# MCU.net
KiCad netlist of a schematic drawn in Altium Designer
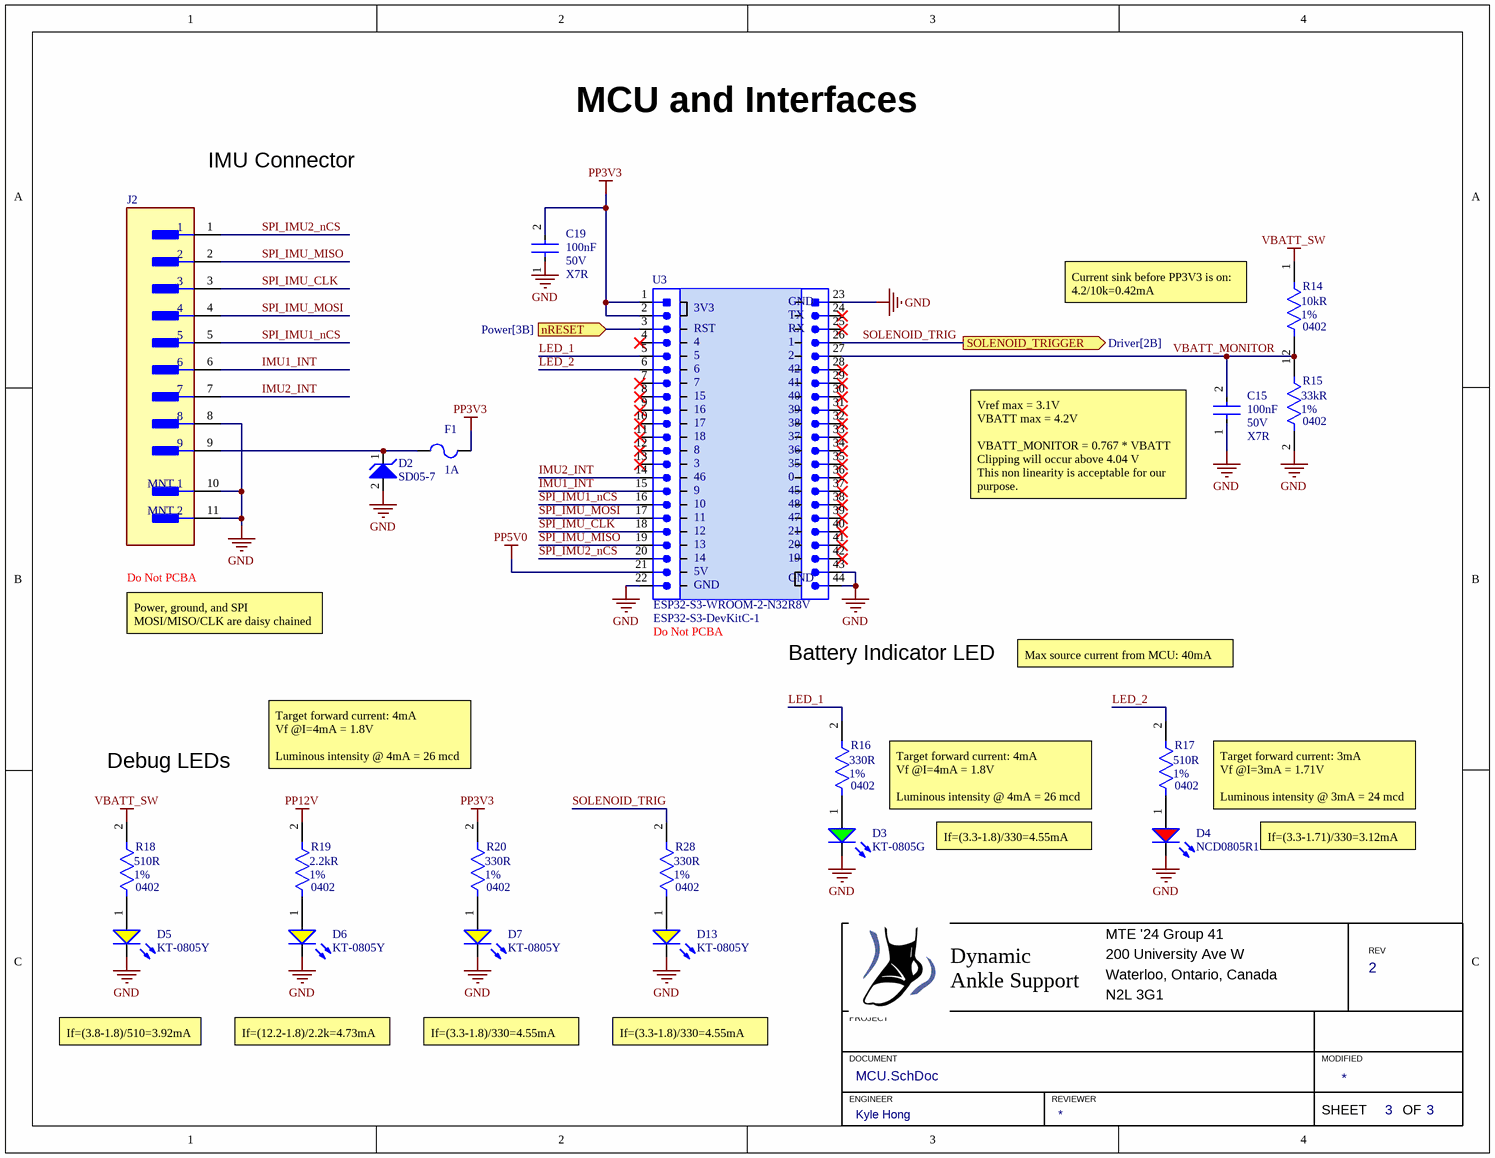
[diagram p0: MCU.SchDoc]

(export (version "E")
  (design (tool "Eeschema 10.0.6"))
  (components
    (comp (ref "C15")
      (value "CL05B104KB54PNC")
      (footprint "CAP0402")
      (description "50V 100nF X7R ±10% 0402  Multilayer Ceramic Capacitors MLCC - SMD/SMT ROHS")
      (fields
        (field (name "TOLERANCE") "±20%")
        (field (name "MANUFACTURER") "Samsung Electro-Mechanics")
        (field (name "DIELECTRIC") "X7R")
        (field (name "VOLTAGE RATING") "50V")
        (field (name "CAPACITANCE") "100nF")
      )
      (libsource (lib "FYDP_library_sch") (part "CAP0402"))
    )
    (comp (ref "C19")
      (value "CL05B104KB54PNC")
      (footprint "CAP0402")
      (description "50V 100nF X7R ±10% 0402  Multilayer Ceramic Capacitors MLCC - SMD/SMT ROHS")
      (fields
        (field (name "TOLERANCE") "±20%")
        (field (name "MANUFACTURER") "Samsung Electro-Mechanics")
        (field (name "DIELECTRIC") "X7R")
        (field (name "VOLTAGE RATING") "50V")
        (field (name "CAPACITANCE") "100nF")
      )
      (libsource (lib "FYDP_library_sch") (part "CAP0402"))
    )
    (comp (ref "D2")
      (value "SD05-7")
      (footprint "SD05-7")
      (description "TVS UNI14.5V 6.2V 5V SOD-323")
      (fields (field (name "MANUFACTURER") "Diodes Incorporated"))
      (libsource (lib "FYDP_library_sch") (part "SD05-7"))
    )
    (comp (ref "D3")
      (value "KT-0805G")
      (footprint "LED_0805_GREEN")
      (description "Emerald 0805  Light Emitting Diodes (LED) ROHS")
      (fields (field (name "MANUFACTURER") "Hubei KENTO Elec"))
      (libsource (lib "FYDP_library_sch") (part "LED_GREEN"))
    )
    (comp (ref "D4")
      (value "NCD0805R1")
      (footprint "LED_0805_RED")
      (fields (field (name "MANUFACTURER") "Foshan NationStar Optoelectronics"))
      (libsource (lib "FYDP_library_sch") (part "LED_RED"))
    )
    (comp (ref "D5")
      (value "KT-0805Y")
      (footprint "LED_0805_YELLOW")
      (description "Yellow 0805  Light Emitting Diodes (LED) ROHS")
      (fields (field (name "MANUFACTURER") "Hubei KENTO Elec"))
      (libsource (lib "FYDP_library_sch") (part "LED_YELLOW"))
    )
    (comp (ref "D6")
      (value "KT-0805Y")
      (footprint "LED_0805_YELLOW")
      (description "Yellow 0805  Light Emitting Diodes (LED) ROHS")
      (fields (field (name "MANUFACTURER") "Hubei KENTO Elec"))
      (libsource (lib "FYDP_library_sch") (part "LED_YELLOW"))
    )
    (comp (ref "D7")
      (value "KT-0805Y")
      (footprint "LED_0805_YELLOW")
      (description "Yellow 0805  Light Emitting Diodes (LED) ROHS")
      (fields (field (name "MANUFACTURER") "Hubei KENTO Elec"))
      (libsource (lib "FYDP_library_sch") (part "LED_YELLOW"))
    )
    (comp (ref "D13")
      (value "KT-0805Y")
      (footprint "LED_0805_YELLOW")
      (description "Yellow 0805  Light Emitting Diodes (LED) ROHS")
      (fields (field (name "MANUFACTURER") "Hubei KENTO Elec"))
      (libsource (lib "FYDP_library_sch") (part "LED_YELLOW"))
    )
    (comp (ref "F1")
      (value "0467001.NRHF")
      (footprint "FUSE_0603")
      (description "50A SMD Fuse 1A 32V 32V 0603  Fuses ROHS")
      (fields (field (name "MANUFACTURER") "Littelfuse") (field (name "CURRENT RATING") "1A"))
      (libsource (lib "FYDP_library_sch") (part "FUSE0603"))
    )
    (comp (ref "J2")
      (value "S9B-PH-SM4-TB(LF)(SN)")
      (footprint "FP-S9B-PH-SM4-TB_LF_SN-MFG")
      (description "CONN HEADER SMD R/A 9POS 2MM")
      (libsource (lib "Altium Content Vault") (part "1768e92021096bf704ffca471e34b85"))
    )
    (comp (ref "R14")
      (value "0402WGF1002TCE")
      (footprint "RES0402")
      (description "62.5mW Thick Film Resistors ±100ppm/℃ ±1% 10kΩ 0402  Chip Resistor - Surface Mount ROHS")
      (fields
        (field (name "MANUFACTURER") "UNI-ROYAL(Uniroyal Elec)")
        (field (name "TOLERANCE") "1%")
        (field (name "RESISTANCE") "10kR")
        (field (name "PACKAGE") "0402")
      )
      (libsource (lib "FYDP_library_sch") (part "RES0402"))
    )
    (comp (ref "R15")
      (value "0402WGF3302TCE")
      (footprint "RES0402")
      (description "62.5mW Thick Film Resistors ±100ppm/℃ ±1% 33kΩ 0402  Chip Resistor - Surface Mount ROHS")
      (fields
        (field (name "MANUFACTURER") "UNI-ROYAL(Uniroyal Elec)")
        (field (name "TOLERANCE") "1%")
        (field (name "RESISTANCE") "33kR")
        (field (name "PACKAGE") "0402")
      )
      (libsource (lib "FYDP_library_sch") (part "RES0402"))
    )
    (comp (ref "R16")
      (value "0402WGF3300TCE")
      (footprint "RES0402")
      (description "62.5mW Thick Film Resistors ±100ppm/℃ ±1% 330Ω 0402  Chip Resistor - Surface Mount ROHS")
      (fields
        (field (name "MANUFACTURER") "UNI-ROYAL(Uniroyal Elec)")
        (field (name "TOLERANCE") "1%")
        (field (name "RESISTANCE") "330R")
        (field (name "PACKAGE") "0402")
      )
      (libsource (lib "FYDP_library_sch") (part "RES0402"))
    )
    (comp (ref "R17")
      (value "0402WGF5100TCE")
      (footprint "RES0402")
      (description "62.5mW Thick Film Resistors ±100ppm/℃ ±1% 510Ω 0402  Chip Resistor - Surface Mount ROHS")
      (fields
        (field (name "MANUFACTURER") "UNI-ROYAL(Uniroyal Elec)")
        (field (name "TOLERANCE") "1%")
        (field (name "RESISTANCE") "510R")
        (field (name "PACKAGE") "0402")
      )
      (libsource (lib "FYDP_library_sch") (part "RES0402"))
    )
    (comp (ref "R18")
      (value "0402WGF5100TCE")
      (footprint "RES0402")
      (description "62.5mW Thick Film Resistors ±100ppm/℃ ±1% 510Ω 0402  Chip Resistor - Surface Mount ROHS")
      (fields
        (field (name "MANUFACTURER") "UNI-ROYAL(Uniroyal Elec)")
        (field (name "TOLERANCE") "1%")
        (field (name "RESISTANCE") "510R")
        (field (name "PACKAGE") "0402")
      )
      (libsource (lib "FYDP_library_sch") (part "RES0402"))
    )
    (comp (ref "R19")
      (value "0402WGF2201TCE")
      (footprint "RES0402")
      (description "62.5mW Thick Film Resistors ±100ppm/℃ ±1% 2.2kΩ 0402  Chip Resistor - Surface Mount ROHS")
      (fields
        (field (name "MANUFACTURER") "UNI-ROYAL(Uniroyal Elec)")
        (field (name "TOLERANCE") "1%")
        (field (name "RESISTANCE") "2.2kR")
        (field (name "PACKAGE") "0402")
      )
      (libsource (lib "FYDP_library_sch") (part "RES0402"))
    )
    (comp (ref "R20")
      (value "0402WGF3300TCE")
      (footprint "RES0402")
      (description "62.5mW Thick Film Resistors ±100ppm/℃ ±1% 330Ω 0402  Chip Resistor - Surface Mount ROHS")
      (fields
        (field (name "MANUFACTURER") "UNI-ROYAL(Uniroyal Elec)")
        (field (name "TOLERANCE") "1%")
        (field (name "RESISTANCE") "330R")
        (field (name "PACKAGE") "0402")
      )
      (libsource (lib "FYDP_library_sch") (part "RES0402"))
    )
    (comp (ref "R28")
      (value "0402WGF3300TCE")
      (footprint "RES0402")
      (description "62.5mW Thick Film Resistors ±100ppm/℃ ±1% 330Ω 0402  Chip Resistor - Surface Mount ROHS")
      (fields
        (field (name "MANUFACTURER") "UNI-ROYAL(Uniroyal Elec)")
        (field (name "TOLERANCE") "1%")
        (field (name "RESISTANCE") "330R")
        (field (name "PACKAGE") "0402")
      )
      (libsource (lib "FYDP_library_sch") (part "RES0402"))
    )
    (comp (ref "U3")
      (value "ESP32-S3-WROOM-2-N32R8V")
      (footprint "EPS32-S3-DevKitC")
      (fields
        (field (name "MCU PART NUMBER") "ESP32-S3-WROOM-2-N32R8V")
        (field (name "DEV KIT PART NUMBER") "ESP32-S3-DevKitC-1")
      )
      (libsource (lib "FYDP_library_sch") (part "EPS32-S3-DevKitC"))
    )
  )
  (nets
    (net (code "1") (name "/IMU1_INT") (class "Default")
      (node (ref "J2") (pin "6") (pinfunction "6_6") (pintype "passive"))
      (node (ref "U3") (pin "15") (pinfunction "15_15") (pintype "passive"))
    )
    (net (code "2") (name "/IMU2_INT") (class "Default")
      (node (ref "J2") (pin "7") (pinfunction "7_7") (pintype "passive"))
      (node (ref "U3") (pin "14") (pinfunction "14_14") (pintype "passive"))
    )
    (net (code "3") (name "/LED_1") (class "Default")
      (node (ref "R16") (pin "2") (pinfunction "2_2") (pintype "passive"))
      (node (ref "U3") (pin "5") (pinfunction "5_5") (pintype "passive"))
    )
    (net (code "4") (name "/LED_2") (class "Default")
      (node (ref "R17") (pin "2") (pinfunction "2_2") (pintype "passive"))
      (node (ref "U3") (pin "6") (pinfunction "6_6") (pintype "passive"))
    )
    (net (code "5") (name "/SOLENOID_TRIG") (class "Default")
      (node (ref "R28") (pin "2") (pinfunction "2_2") (pintype "passive"))
      (node (ref "U3") (pin "26") (pinfunction "26_26") (pintype "passive"))
    )
    (net (code "6") (name "/SPI_IMU1_nCS") (class "Default")
      (node (ref "J2") (pin "5") (pinfunction "5_5") (pintype "passive"))
      (node (ref "U3") (pin "16") (pinfunction "16_16") (pintype "passive"))
    )
    (net (code "7") (name "/SPI_IMU2_nCS") (class "Default")
      (node (ref "J2") (pin "1") (pinfunction "1_1") (pintype "passive"))
      (node (ref "U3") (pin "20") (pinfunction "20_20") (pintype "passive"))
    )
    (net (code "8") (name "/SPI_IMU_CLK") (class "Default")
      (node (ref "J2") (pin "3") (pinfunction "3_3") (pintype "passive"))
      (node (ref "U3") (pin "18") (pinfunction "18_18") (pintype "passive"))
    )
    (net (code "9") (name "/SPI_IMU_MISO") (class "Default")
      (node (ref "J2") (pin "2") (pinfunction "2_2") (pintype "passive"))
      (node (ref "U3") (pin "19") (pinfunction "19_19") (pintype "passive"))
    )
    (net (code "10") (name "/SPI_IMU_MOSI") (class "Default")
      (node (ref "J2") (pin "4") (pinfunction "4_4") (pintype "passive"))
      (node (ref "U3") (pin "17") (pinfunction "17_17") (pintype "passive"))
    )
    (net (code "11") (name "/VBATT_MONITOR") (class "Default")
      (node (ref "C15") (pin "2") (pinfunction "2_2") (pintype "passive"))
      (node (ref "R14") (pin "2") (pinfunction "2_2") (pintype "passive"))
      (node (ref "R15") (pin "1") (pinfunction "1_1") (pintype "passive"))
      (node (ref "U3") (pin "27") (pinfunction "27_27") (pintype "passive"))
    )
    (net (code "12") (name "/nRESET") (class "Default")
      (node (ref "U3") (pin "3") (pinfunction "3_3") (pintype "passive"))
    )
    (net (code "13") (name "GND") (class "Default")
      (node (ref "C15") (pin "1") (pinfunction "1_1") (pintype "passive"))
      (node (ref "C19") (pin "1") (pinfunction "1_1") (pintype "passive"))
      (node (ref "D13") (pin "1") (pinfunction "K_1") (pintype "passive"))
      (node (ref "D2") (pin "2") (pinfunction "2_2") (pintype "passive"))
      (node (ref "D3") (pin "1") (pinfunction "K_1") (pintype "passive"))
      (node (ref "D4") (pin "1") (pinfunction "K_1") (pintype "passive"))
      (node (ref "D5") (pin "1") (pinfunction "K_1") (pintype "passive"))
      (node (ref "D6") (pin "1") (pinfunction "K_1") (pintype "passive"))
      (node (ref "D7") (pin "1") (pinfunction "K_1") (pintype "passive"))
      (node (ref "J2") (pin "10") (pinfunction "MNT_1_10") (pintype "passive"))
      (node (ref "J2") (pin "11") (pinfunction "MNT_2_11") (pintype "passive"))
      (node (ref "J2") (pin "8") (pinfunction "8_8") (pintype "passive"))
      (node (ref "R15") (pin "2") (pinfunction "2_2") (pintype "passive"))
      (node (ref "U3") (pin "22") (pinfunction "22_22") (pintype "passive"))
      (node (ref "U3") (pin "23") (pinfunction "23_23") (pintype "passive"))
      (node (ref "U3") (pin "43") (pinfunction "43_43") (pintype "passive"))
      (node (ref "U3") (pin "44") (pinfunction "44_44") (pintype "passive"))
    )
    (net (code "14") (name "Net-(D2-Pad1)") (class "Default")
      (node (ref "D2") (pin "1") (pinfunction "1_1") (pintype "passive"))
      (node (ref "F1") (pin "1") (pinfunction "1_1") (pintype "passive"))
      (node (ref "J2") (pin "9") (pinfunction "9_9") (pintype "passive"))
    )
    (net (code "15") (name "Net-(D3-A)") (class "Default")
      (node (ref "D3") (pin "2") (pinfunction "A_2") (pintype "passive"))
      (node (ref "R16") (pin "1") (pinfunction "1_1") (pintype "passive"))
    )
    (net (code "16") (name "Net-(D4-A)") (class "Default")
      (node (ref "D4") (pin "2") (pinfunction "A_2") (pintype "passive"))
      (node (ref "R17") (pin "1") (pinfunction "1_1") (pintype "passive"))
    )
    (net (code "17") (name "Net-(D5-A)") (class "Default")
      (node (ref "D5") (pin "2") (pinfunction "A_2") (pintype "passive"))
      (node (ref "R18") (pin "1") (pinfunction "1_1") (pintype "passive"))
    )
    (net (code "18") (name "Net-(D6-A)") (class "Default")
      (node (ref "D6") (pin "2") (pinfunction "A_2") (pintype "passive"))
      (node (ref "R19") (pin "1") (pinfunction "1_1") (pintype "passive"))
    )
    (net (code "19") (name "Net-(D7-A)") (class "Default")
      (node (ref "D7") (pin "2") (pinfunction "A_2") (pintype "passive"))
      (node (ref "R20") (pin "1") (pinfunction "1_1") (pintype "passive"))
    )
    (net (code "20") (name "Net-(D13-A)") (class "Default")
      (node (ref "D13") (pin "2") (pinfunction "A_2") (pintype "passive"))
      (node (ref "R28") (pin "1") (pinfunction "1_1") (pintype "passive"))
    )
    (net (code "21") (name "PP3V3") (class "Default")
      (node (ref "C19") (pin "2") (pinfunction "2_2") (pintype "passive"))
      (node (ref "F1") (pin "2") (pinfunction "2_2") (pintype "passive"))
      (node (ref "R20") (pin "2") (pinfunction "2_2") (pintype "passive"))
      (node (ref "U3") (pin "1") (pinfunction "1_1") (pintype "passive"))
      (node (ref "U3") (pin "2") (pinfunction "2_2") (pintype "passive"))
    )
    (net (code "22") (name "PP5V0") (class "Default")
      (node (ref "U3") (pin "21") (pinfunction "21_21") (pintype "passive"))
    )
    (net (code "23") (name "PP12V") (class "Default")
      (node (ref "R19") (pin "2") (pinfunction "2_2") (pintype "passive"))
    )
    (net (code "24") (name "VBATT_SW") (class "Default")
      (node (ref "R14") (pin "1") (pinfunction "1_1") (pintype "passive"))
      (node (ref "R18") (pin "2") (pinfunction "2_2") (pintype "passive"))
    )
    (net (code "25") (name "unconnected-(U3-6-Pad7)") (class "Default")
      (node (ref "U3") (pin "7") (pinfunction "6_7") (pintype "passive+no_connect"))
    )
    (net (code "26") (name "unconnected-(U3-6-Pad8)") (class "Default")
      (node (ref "U3") (pin "8") (pinfunction "6_8") (pintype "passive+no_connect"))
    )
    (net (code "27") (name "unconnected-(U3-Pad4)") (class "Default")
      (node (ref "U3") (pin "4") (pinfunction "4_4") (pintype "passive+no_connect"))
    )
    (net (code "28") (name "unconnected-(U3-Pad9)") (class "Default")
      (node (ref "U3") (pin "9") (pinfunction "9_9") (pintype "passive+no_connect"))
    )
    (net (code "29") (name "unconnected-(U3-Pad10)") (class "Default")
      (node (ref "U3") (pin "10") (pinfunction "10_10") (pintype "passive+no_connect"))
    )
    (net (code "30") (name "unconnected-(U3-Pad11)") (class "Default")
      (node (ref "U3") (pin "11") (pinfunction "11_11") (pintype "passive+no_connect"))
    )
    (net (code "31") (name "unconnected-(U3-Pad12)") (class "Default")
      (node (ref "U3") (pin "12") (pinfunction "12_12") (pintype "passive+no_connect"))
    )
    (net (code "32") (name "unconnected-(U3-Pad13)") (class "Default")
      (node (ref "U3") (pin "13") (pinfunction "13_13") (pintype "passive+no_connect"))
    )
    (net (code "33") (name "unconnected-(U3-Pad24)") (class "Default")
      (node (ref "U3") (pin "24") (pinfunction "24_24") (pintype "passive+no_connect"))
    )
    (net (code "34") (name "unconnected-(U3-Pad25)") (class "Default")
      (node (ref "U3") (pin "25") (pinfunction "25_25") (pintype "passive+no_connect"))
    )
    (net (code "35") (name "unconnected-(U3-Pad28)") (class "Default")
      (node (ref "U3") (pin "28") (pinfunction "28_28") (pintype "passive+no_connect"))
    )
    (net (code "36") (name "unconnected-(U3-Pad29)") (class "Default")
      (node (ref "U3") (pin "29") (pinfunction "29_29") (pintype "passive+no_connect"))
    )
    (net (code "37") (name "unconnected-(U3-Pad30)") (class "Default")
      (node (ref "U3") (pin "30") (pinfunction "30_30") (pintype "passive+no_connect"))
    )
    (net (code "38") (name "unconnected-(U3-Pad31)") (class "Default")
      (node (ref "U3") (pin "31") (pinfunction "31_31") (pintype "passive+no_connect"))
    )
    (net (code "39") (name "unconnected-(U3-Pad32)") (class "Default")
      (node (ref "U3") (pin "32") (pinfunction "32_32") (pintype "passive+no_connect"))
    )
    (net (code "40") (name "unconnected-(U3-Pad33)") (class "Default")
      (node (ref "U3") (pin "33") (pinfunction "33_33") (pintype "passive+no_connect"))
    )
    (net (code "41") (name "unconnected-(U3-Pad34)") (class "Default")
      (node (ref "U3") (pin "34") (pinfunction "34_34") (pintype "passive+no_connect"))
    )
    (net (code "42") (name "unconnected-(U3-Pad35)") (class "Default")
      (node (ref "U3") (pin "35") (pinfunction "35_35") (pintype "passive+no_connect"))
    )
    (net (code "43") (name "unconnected-(U3-Pad36)") (class "Default")
      (node (ref "U3") (pin "36") (pinfunction "36_36") (pintype "passive+no_connect"))
    )
    (net (code "44") (name "unconnected-(U3-Pad37)") (class "Default")
      (node (ref "U3") (pin "37") (pinfunction "37_37") (pintype "passive+no_connect"))
    )
    (net (code "45") (name "unconnected-(U3-Pad38)") (class "Default")
      (node (ref "U3") (pin "38") (pinfunction "38_38") (pintype "passive+no_connect"))
    )
    (net (code "46") (name "unconnected-(U3-Pad39)") (class "Default")
      (node (ref "U3") (pin "39") (pinfunction "39_39") (pintype "passive+no_connect"))
    )
    (net (code "47") (name "unconnected-(U3-Pad40)") (class "Default")
      (node (ref "U3") (pin "40") (pinfunction "40_40") (pintype "passive+no_connect"))
    )
    (net (code "48") (name "unconnected-(U3-Pad41)") (class "Default")
      (node (ref "U3") (pin "41") (pinfunction "41_41") (pintype "passive+no_connect"))
    )
    (net (code "49") (name "unconnected-(U3-Pad42)") (class "Default")
      (node (ref "U3") (pin "42") (pinfunction "42_42") (pintype "passive+no_connect"))
    )
  )
)
